# H12R00.net
KiCad netlist of a schematic drawn in EAGLE
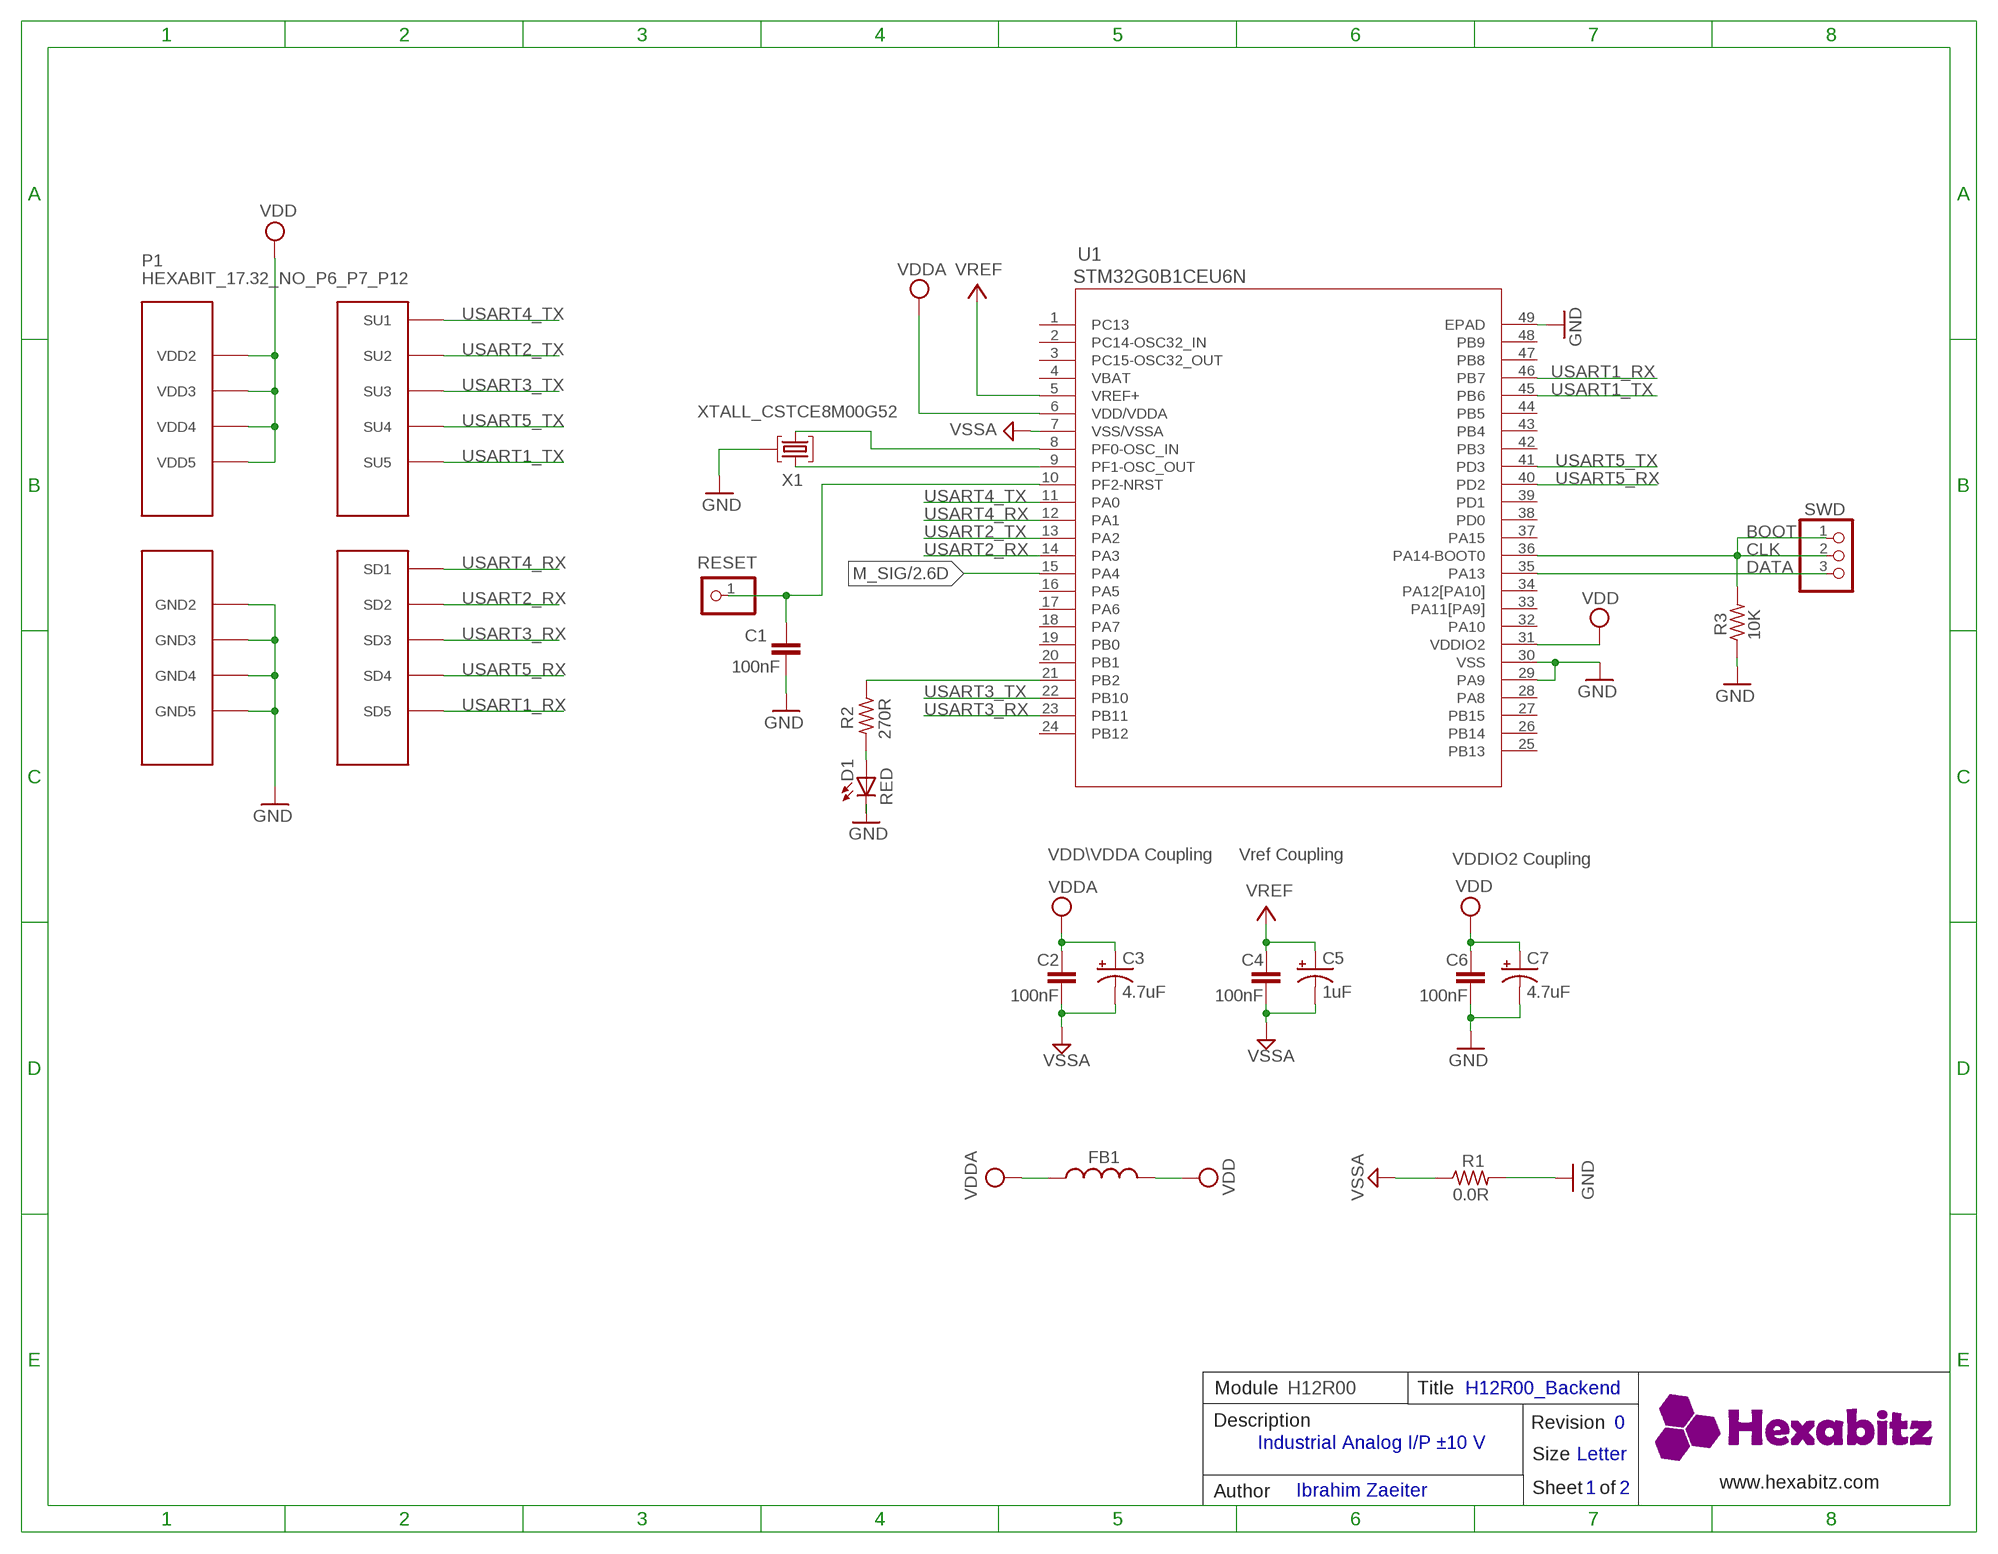
[diagram p0: schematic, sheet 1]
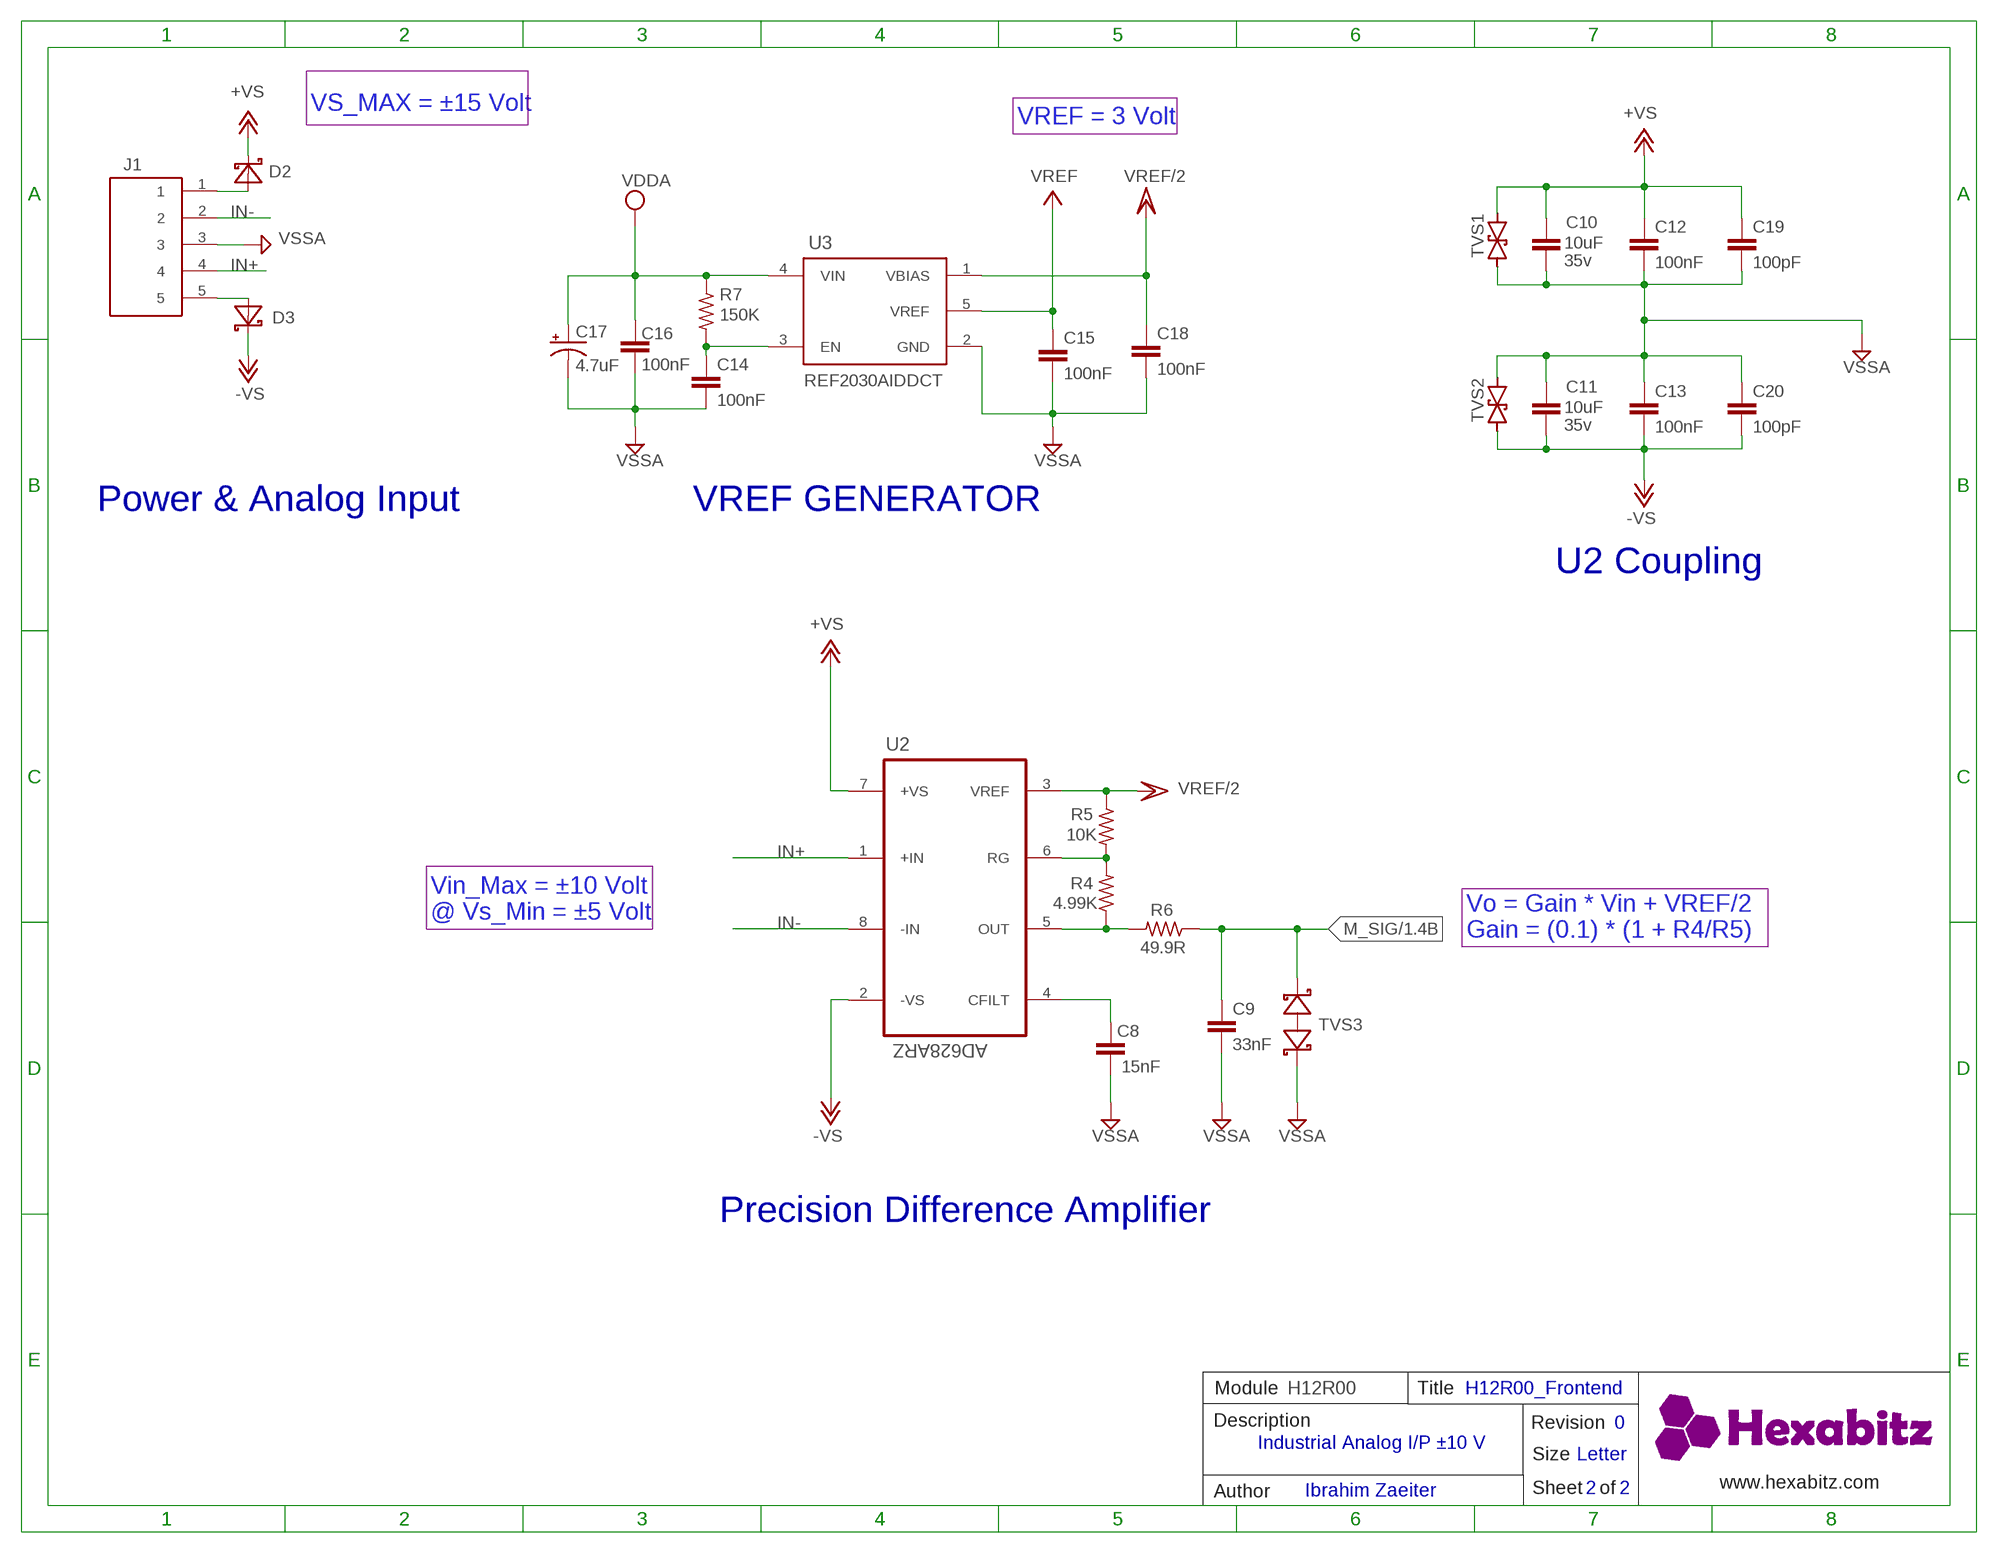
[diagram p1: schematic, sheet 2]

(export (version "E")
  (design (tool "Eeschema 10.0.6"))
  (components
    (comp (ref "C1")
      (value "100nF")
      (footprint "eagle-import:C-0603")
      (libsource (lib "eagle-import") (part "C-0603"))
    )
    (comp (ref "C2")
      (value "100nF")
      (footprint "eagle-import:C-0603")
      (libsource (lib "eagle-import") (part "C-0603"))
    )
    (comp (ref "C3")
      (value "4.7uF")
      (footprint "eagle-import:C-0805-POL")
      (libsource (lib "eagle-import") (part "C-0805-POL"))
    )
    (comp (ref "C4")
      (value "100nF")
      (footprint "eagle-import:C-0603")
      (libsource (lib "eagle-import") (part "C-0603"))
    )
    (comp (ref "C5")
      (value "1uF")
      (footprint "eagle-import:C-0805-POL")
      (libsource (lib "eagle-import") (part "C-0805-POL"))
    )
    (comp (ref "C6")
      (value "100nF")
      (footprint "eagle-import:C-0603")
      (libsource (lib "eagle-import") (part "C-0603"))
    )
    (comp (ref "C7")
      (value "4.7uF")
      (footprint "eagle-import:C-0805-POL")
      (libsource (lib "eagle-import") (part "C-0805-POL"))
    )
    (comp (ref "D1")
      (value "RED")
      (footprint "eagle-import:VLMS1300-GS08")
      (fields
        (field (name "MPN") "VLMS1300-GS08")
        (field (name "MFN") "Vishay")
        (field (name "MPN_1") "VLMS1300-GS08")
        (field (name "OCTOPART_URL") "https://octopart.com/vlms1300-gs08-vishay-21709201?r=sp&s=_gcP4_q8T1SC6PJQPTQ9yA")
      )
      (libsource (lib "eagle-import") (part "VLMS1300-GS08"))
    )
    (comp (ref "FB1")
      (value "FB-0603")
      (footprint "eagle-import:FB-0603")
      (libsource (lib "eagle-import") (part "FB-0603"))
    )
    (comp (ref "P1")
      (value "HEXABIT_17.32_NO_P6_P7_P12")
      (footprint "eagle-import:HEXABIT_17.32_NO_P6_P7_P12")
      (libsource (lib "eagle-import") (part "HEXABIT_?_NO_P6_P7_P1217.32"))
    )
    (comp (ref "R1")
      (value "0.0R")
      (footprint "eagle-import:R-0603")
      (libsource (lib "eagle-import") (part "R-0603"))
    )
    (comp (ref "R2")
      (value "270R")
      (footprint "eagle-import:R-0603")
      (libsource (lib "eagle-import") (part "R-0603"))
    )
    (comp (ref "R3")
      (value "10K")
      (footprint "eagle-import:R-0603")
      (libsource (lib "eagle-import") (part "R-0603"))
    )
    (comp (ref "RESET")
      (value "R")
      (footprint "eagle-import:1X01")
      (fields (field (name "MPN") "87227-1"))
      (libsource (lib "eagle-import") (part "PINHD-1X1"))
    )
    (comp (ref "SWD")
      (value "PINHD-1X3SWD")
      (footprint "eagle-import:SWD")
      (libsource (lib "eagle-import") (part "PINHD-1X3SWD"))
    )
    (comp (ref "U1")
      (value "STM32G0B1CEU6N")
      (footprint "eagle-import:HEXABITZ_ICS_QFN_B1CEU6_STM-L")
      (libsource (lib "eagle-import") (part "STM32G0B1CEU6N"))
    )
    (comp (ref "X1")
      (value "XTALL_CSTCE8M00G52")
      (footprint "eagle-import:XTALL_CSTCE8M00G52")
      (fields (field (name "MPN") "CSTCE8M00G52Z-R0"))
      (libsource (lib "eagle-import") (part "XTALL_CSTCE8M00G52"))
    )
    (comp (ref "C8")
      (value "15nF")
      (footprint "eagle-import:C-0603")
      (libsource (lib "eagle-import") (part "C-0603"))
    )
    (comp (ref "C9")
      (value "33nF")
      (footprint "eagle-import:C-0603")
      (libsource (lib "eagle-import") (part "C-0603"))
    )
    (comp (ref "C10")
      (value "C-0805")
      (footprint "eagle-import:C-0805")
      (fields
        (field (name "CAPACITANCE") "10uF")
        (field (name "MPN") "GRM21BR6YA106ME43K")
        (field (name "VOLTAGE_RATING") "35v")
      )
      (libsource (lib "eagle-import") (part "C-0805"))
    )
    (comp (ref "C11")
      (value "C-0805")
      (footprint "eagle-import:C-0805")
      (fields
        (field (name "CAPACITANCE") "10uF")
        (field (name "MPN") "GRM21BR6YA106ME43K")
        (field (name "VOLTAGE_RATING") "35v")
      )
      (libsource (lib "eagle-import") (part "C-0805"))
    )
    (comp (ref "C12")
      (value "100nF")
      (footprint "eagle-import:C-0603")
      (fields (field (name "MPN") "C1608X7R1H104K080AA"))
      (libsource (lib "eagle-import") (part "C-0603"))
    )
    (comp (ref "C13")
      (value "100nF")
      (footprint "eagle-import:C-0603")
      (fields (field (name "MPN") "C1608X7R1H104K080AA"))
      (libsource (lib "eagle-import") (part "C-0603"))
    )
    (comp (ref "C14")
      (value "100nF")
      (footprint "eagle-import:C-0603")
      (libsource (lib "eagle-import") (part "C-0603"))
    )
    (comp (ref "C15")
      (value "100nF")
      (footprint "eagle-import:C-0603")
      (libsource (lib "eagle-import") (part "C-0603"))
    )
    (comp (ref "C16")
      (value "100nF")
      (footprint "eagle-import:C-0603")
      (libsource (lib "eagle-import") (part "C-0603"))
    )
    (comp (ref "C17")
      (value "4.7uF")
      (footprint "eagle-import:C-0805-POL")
      (libsource (lib "eagle-import") (part "C-0805-POL"))
    )
    (comp (ref "C18")
      (value "100nF")
      (footprint "eagle-import:C-0603")
      (libsource (lib "eagle-import") (part "C-0603"))
    )
    (comp (ref "C19")
      (value "100pF")
      (footprint "eagle-import:C-0603")
      (fields (field (name "MPN") "C1608X7R1H104K080AA"))
      (libsource (lib "eagle-import") (part "C-0603"))
    )
    (comp (ref "C20")
      (value "100pF")
      (footprint "eagle-import:C-0603")
      (fields (field (name "MPN") "C1608X7R1H104K080AA"))
      (libsource (lib "eagle-import") (part "C-0603"))
    )
    (comp (ref "D2")
      (value "DIOD-SOD-123")
      (footprint "eagle-import:SOD123")
      (libsource (lib "eagle-import") (part "DIOD-SOD-123"))
    )
    (comp (ref "D3")
      (value "DIOD-SOD-123")
      (footprint "eagle-import:SOD123")
      (libsource (lib "eagle-import") (part "DIOD-SOD-123"))
    )
    (comp (ref "J1")
      (value "1984646")
      (footprint "eagle-import:1984646")
      (fields (field (name "MOUSER_PART_NUMBER") "651-1984646"))
      (libsource (lib "eagle-import") (part "1984646"))
    )
    (comp (ref "R4")
      (value "4.99K")
      (footprint "eagle-import:R-0603")
      (libsource (lib "eagle-import") (part "R-0603"))
    )
    (comp (ref "R5")
      (value "10K")
      (footprint "eagle-import:R-0603")
      (libsource (lib "eagle-import") (part "R-0603"))
    )
    (comp (ref "R6")
      (value "49.9R")
      (footprint "eagle-import:R-0603")
      (libsource (lib "eagle-import") (part "R-0603"))
    )
    (comp (ref "R7")
      (value "150K")
      (footprint "eagle-import:R-0603")
      (libsource (lib "eagle-import") (part "R-0603"))
    )
    (comp (ref "TVS1")
      (value "SMBJ30CA")
      (footprint "eagle-import:DO214AA")
      (libsource (lib "eagle-import") (part "SMBJ30CA"))
    )
    (comp (ref "TVS2")
      (value "SMBJ30CA")
      (footprint "eagle-import:DO214AA")
      (libsource (lib "eagle-import") (part "SMBJ30CA"))
    )
    (comp (ref "TVS3")
      (value "BOURNS_CDSOD323-T03SCBOURNS_CDSOD323-T03SC_0_0")
      (footprint "eagle-import:BOURNS_CDSOD323-T03SC_0")
      (fields (field (name "MPN") "CDSOD323-T03SC"))
      (libsource (lib "eagle-import") (part "BOURNS_CDSOD323-T03SCBOURNS_CDSOD323-T03SC_0_0"))
    )
    (comp (ref "U2")
      (value "AD628ARZ")
      (footprint "eagle-import:SOIC127P600X175-8N")
      (libsource (lib "eagle-import") (part "AD628ARZ"))
    )
    (comp (ref "U3")
      (value "TEXAS_INSTRUMENTS_REF2033AIDDCRTEXAS_INSTRUMENTS_REF2033AIDDCR_0_2")
      (footprint "eagle-import:TEXAS_INSTRUMENTS_REF2033AIDDCR_2")
      (fields
        (field (name "MPN") "REF2033AIDDCR")
        (field (name "MPN_1") "REF2030AIDDCT")
        (field (name "OUTPUT_VOLTAGE") "1.5/3.0V")
      )
      (libsource (lib "eagle-import") (part "TEXAS_INSTRUMENTS_REF2033AIDDCRTEXAS_INSTRUMENTS_REF2033AIDDCR_0_2"))
    )
  )
  (nets
    (net (code "1") (name "+VS") (class "Default")
      (node (ref "C10") (pin "1") (pinfunction "1_1") (pintype "passive"))
      (node (ref "C12") (pin "1") (pinfunction "1_1") (pintype "passive"))
      (node (ref "C19") (pin "1") (pinfunction "1_1") (pintype "passive"))
      (node (ref "D2") (pin "2") (pinfunction "C_2") (pintype "passive"))
      (node (ref "TVS1") (pin "C") (pinfunction "2_C") (pintype "passive"))
      (node (ref "U2") (pin "7") (pinfunction "+VS_7") (pintype "power_in"))
    )
    (net (code "2") (name "-VS") (class "Default")
      (node (ref "C11") (pin "2") (pinfunction "2_2") (pintype "passive"))
      (node (ref "C13") (pin "2") (pinfunction "2_2") (pintype "passive"))
      (node (ref "C20") (pin "2") (pinfunction "2_2") (pintype "passive"))
      (node (ref "D3") (pin "2") (pinfunction "C_2") (pintype "passive"))
      (node (ref "TVS2") (pin "A") (pinfunction "1_A") (pintype "passive"))
      (node (ref "U2") (pin "2") (pinfunction "-VS_2") (pintype "power_in"))
    )
    (net (code "3") (name "CLK") (class "Default")
      (node (ref "R3") (pin "2") (pinfunction "2_2") (pintype "passive"))
      (node (ref "SWD") (pin "1") (pinfunction "1_1") (pintype "passive"))
      (node (ref "SWD") (pin "2") (pinfunction "2_2") (pintype "passive"))
      (node (ref "U1") (pin "36") (pinfunction "PA14-BOOT0_36") (pintype "bidirectional"))
    )
    (net (code "4") (name "DATA") (class "Default")
      (node (ref "SWD") (pin "3") (pinfunction "3_3") (pintype "passive"))
      (node (ref "U1") (pin "35") (pinfunction "PA13_35") (pintype "bidirectional"))
    )
    (net (code "5") (name "GND") (class "Default")
      (node (ref "C1") (pin "2") (pinfunction "2_2") (pintype "passive"))
      (node (ref "C6") (pin "2") (pinfunction "2_2") (pintype "passive"))
      (node (ref "C7") (pin "2") (pinfunction "-_2") (pintype "passive"))
      (node (ref "D1") (pin "C") (pinfunction "C_C") (pintype "passive"))
      (node (ref "P1") (pin "PAD_PD10") (pinfunction "GND4_PAD_PD10") (pintype "power_in"))
      (node (ref "P1") (pin "PAD_PD11") (pinfunction "GND5_PAD_PD11") (pintype "power_in"))
      (node (ref "P1") (pin "PAD_PD8") (pinfunction "GND2_PAD_PD8") (pintype "power_in"))
      (node (ref "P1") (pin "PAD_PD9") (pinfunction "GND3_PAD_PD9") (pintype "power_in"))
      (node (ref "R1") (pin "2") (pinfunction "2_2") (pintype "passive"))
      (node (ref "R3") (pin "1") (pinfunction "1_1") (pintype "passive"))
      (node (ref "U1") (pin "29") (pinfunction "PA9_29") (pintype "bidirectional"))
      (node (ref "U1") (pin "30") (pinfunction "VSS_30") (pintype "passive"))
      (node (ref "U1") (pin "49") (pinfunction "EPAD_49") (pintype "passive"))
      (node (ref "X1") (pin "P$2") (pinfunction "2_P$2") (pintype "passive"))
    )
    (net (code "6") (name "IN+") (class "Default")
      (node (ref "J1") (pin "4") (pinfunction "4_4") (pintype "bidirectional"))
      (node (ref "U2") (pin "1") (pinfunction "+IN_1") (pintype "input"))
    )
    (net (code "7") (name "IN-") (class "Default")
      (node (ref "J1") (pin "2") (pinfunction "2_2") (pintype "bidirectional"))
      (node (ref "U2") (pin "8") (pinfunction "-IN_8") (pintype "input"))
    )
    (net (code "8") (name "M_SIG") (class "Default")
      (node (ref "C9") (pin "1") (pinfunction "1_1") (pintype "passive"))
      (node (ref "R6") (pin "1") (pinfunction "1_1") (pintype "passive"))
      (node (ref "TVS3") (pin "2") (pinfunction "C_2") (pintype "passive"))
      (node (ref "U1") (pin "15") (pinfunction "PA4_15") (pintype "bidirectional"))
    )
    (net (code "9") (name "Net-(D1-PadA)") (class "Default")
      (node (ref "D1") (pin "A") (pinfunction "A_A") (pintype "passive"))
      (node (ref "R2") (pin "2") (pinfunction "2_2") (pintype "passive"))
    )
    (net (code "10") (name "Net-(D2-A)") (class "Default")
      (node (ref "D2") (pin "1") (pinfunction "A_1") (pintype "passive"))
      (node (ref "J1") (pin "1") (pinfunction "1_1") (pintype "bidirectional"))
    )
    (net (code "11") (name "Net-(D3-A)") (class "Default")
      (node (ref "D3") (pin "1") (pinfunction "A_1") (pintype "passive"))
      (node (ref "J1") (pin "5") (pinfunction "5_5") (pintype "bidirectional"))
    )
    (net (code "12") (name "Net-(U1-PB2)") (class "Default")
      (node (ref "R2") (pin "1") (pinfunction "1_1") (pintype "passive"))
      (node (ref "U1") (pin "21") (pinfunction "PB2_21") (pintype "bidirectional"))
    )
    (net (code "13") (name "Net-(U1-PF0-OSC_IN)") (class "Default")
      (node (ref "U1") (pin "8") (pinfunction "PF0-OSC_IN_8") (pintype "bidirectional"))
      (node (ref "X1") (pin "P$3") (pinfunction "3_P$3") (pintype "passive"))
    )
    (net (code "14") (name "Net-(U1-PF1-OSC_OUT)") (class "Default")
      (node (ref "U1") (pin "9") (pinfunction "PF1-OSC_OUT_9") (pintype "bidirectional"))
      (node (ref "X1") (pin "P$1") (pinfunction "1_P$1") (pintype "passive"))
    )
    (net (code "15") (name "Net-(U1-PF2-NRST)") (class "Default")
      (node (ref "C1") (pin "1") (pinfunction "1_1") (pintype "passive"))
      (node (ref "RESET") (pin "1") (pinfunction "1_1") (pintype "passive"))
      (node (ref "U1") (pin "10") (pinfunction "PF2-NRST_10") (pintype "bidirectional"))
    )
    (net (code "16") (name "Net-(U2-CFILT)") (class "Default")
      (node (ref "C8") (pin "1") (pinfunction "1_1") (pintype "passive"))
      (node (ref "U2") (pin "4") (pinfunction "CFILT_4") (pintype "passive"))
    )
    (net (code "17") (name "Net-(U2-OUT)") (class "Default")
      (node (ref "R4") (pin "1") (pinfunction "1_1") (pintype "passive"))
      (node (ref "R6") (pin "2") (pinfunction "2_2") (pintype "passive"))
      (node (ref "U2") (pin "5") (pinfunction "OUT_5") (pintype "output"))
    )
    (net (code "18") (name "Net-(U2-RG)") (class "Default")
      (node (ref "R4") (pin "2") (pinfunction "2_2") (pintype "passive"))
      (node (ref "R5") (pin "2") (pinfunction "2_2") (pintype "passive"))
      (node (ref "U2") (pin "6") (pinfunction "RG_6") (pintype "passive"))
    )
    (net (code "19") (name "Net-(U3-EN)") (class "Default")
      (node (ref "C14") (pin "1") (pinfunction "1_1") (pintype "passive"))
      (node (ref "R7") (pin "2") (pinfunction "2_2") (pintype "passive"))
      (node (ref "U3") (pin "3") (pinfunction "EN_3") (pintype "input"))
    )
    (net (code "20") (name "USART1_RX") (class "Default")
      (node (ref "P1") (pin "PAD_PD5") (pinfunction "SD5_PAD_PD5") (pintype "bidirectional"))
      (node (ref "U1") (pin "46") (pinfunction "PB7_46") (pintype "bidirectional"))
    )
    (net (code "21") (name "USART1_TX") (class "Default")
      (node (ref "P1") (pin "PAD_PU5") (pinfunction "SU5_PAD_PU5") (pintype "bidirectional"))
      (node (ref "U1") (pin "45") (pinfunction "PB6_45") (pintype "bidirectional"))
    )
    (net (code "22") (name "USART2_RX") (class "Default")
      (node (ref "P1") (pin "PAD_PD2") (pinfunction "SD2_PAD_PD2") (pintype "bidirectional"))
      (node (ref "U1") (pin "14") (pinfunction "PA3_14") (pintype "bidirectional"))
    )
    (net (code "23") (name "USART2_TX") (class "Default")
      (node (ref "P1") (pin "PAD_PU2") (pinfunction "SU2_PAD_PU2") (pintype "bidirectional"))
      (node (ref "U1") (pin "13") (pinfunction "PA2_13") (pintype "bidirectional"))
    )
    (net (code "24") (name "USART3_RX") (class "Default")
      (node (ref "P1") (pin "PAD_PD3") (pinfunction "SD3_PAD_PD3") (pintype "bidirectional"))
      (node (ref "U1") (pin "23") (pinfunction "PB11_23") (pintype "bidirectional"))
    )
    (net (code "25") (name "USART3_TX") (class "Default")
      (node (ref "P1") (pin "PAD_PU3") (pinfunction "SU3_PAD_PU3") (pintype "bidirectional"))
      (node (ref "U1") (pin "22") (pinfunction "PB10_22") (pintype "bidirectional"))
    )
    (net (code "26") (name "USART4_RX") (class "Default")
      (node (ref "P1") (pin "PAD_PD1") (pinfunction "SD1_PAD_PD1") (pintype "bidirectional"))
      (node (ref "U1") (pin "12") (pinfunction "PA1_12") (pintype "bidirectional"))
    )
    (net (code "27") (name "USART4_TX") (class "Default")
      (node (ref "P1") (pin "PAD_PU1") (pinfunction "SU1_PAD_PU1") (pintype "bidirectional"))
      (node (ref "U1") (pin "11") (pinfunction "PA0_11") (pintype "bidirectional"))
    )
    (net (code "28") (name "USART5_RX") (class "Default")
      (node (ref "P1") (pin "PAD_PD4") (pinfunction "SD4_PAD_PD4") (pintype "bidirectional"))
      (node (ref "U1") (pin "40") (pinfunction "PD2_40") (pintype "bidirectional"))
    )
    (net (code "29") (name "USART5_TX") (class "Default")
      (node (ref "P1") (pin "PAD_PU4") (pinfunction "SU4_PAD_PU4") (pintype "bidirectional"))
      (node (ref "U1") (pin "41") (pinfunction "PD3_41") (pintype "bidirectional"))
    )
    (net (code "30") (name "VBAT") (class "Default")
      (node (ref "U1") (pin "4") (pinfunction "VBAT_4") (pintype "power_in"))
    )
    (net (code "31") (name "VDD") (class "Default")
      (node (ref "C6") (pin "1") (pinfunction "1_1") (pintype "passive"))
      (node (ref "C7") (pin "1") (pinfunction "+_1") (pintype "passive"))
      (node (ref "FB1") (pin "2") (pinfunction "2_2") (pintype "passive"))
      (node (ref "P1") (pin "PAD_PU10") (pinfunction "VDD4_PAD_PU10") (pintype "power_in"))
      (node (ref "P1") (pin "PAD_PU11") (pinfunction "VDD5_PAD_PU11") (pintype "power_in"))
      (node (ref "P1") (pin "PAD_PU8") (pinfunction "VDD2_PAD_PU8") (pintype "power_in"))
      (node (ref "P1") (pin "PAD_PU9") (pinfunction "VDD3_PAD_PU9") (pintype "power_in"))
      (node (ref "U1") (pin "31") (pinfunction "VDDIO2_31") (pintype "power_in"))
    )
    (net (code "32") (name "VDDA") (class "Default")
      (node (ref "C16") (pin "1") (pinfunction "1_1") (pintype "passive"))
      (node (ref "C17") (pin "1") (pinfunction "+_1") (pintype "passive"))
      (node (ref "C2") (pin "1") (pinfunction "1_1") (pintype "passive"))
      (node (ref "C3") (pin "1") (pinfunction "+_1") (pintype "passive"))
      (node (ref "FB1") (pin "1") (pinfunction "1_1") (pintype "passive"))
      (node (ref "R7") (pin "1") (pinfunction "1_1") (pintype "passive"))
      (node (ref "U1") (pin "6") (pinfunction "VDD/VDDA_6") (pintype "power_in"))
      (node (ref "U3") (pin "4") (pinfunction "VIN_4") (pintype "power_in"))
    )
    (net (code "33") (name "VREF") (class "Default")
      (node (ref "C15") (pin "1") (pinfunction "1_1") (pintype "passive"))
      (node (ref "C4") (pin "1") (pinfunction "1_1") (pintype "passive"))
      (node (ref "C5") (pin "1") (pinfunction "+_1") (pintype "passive"))
      (node (ref "U1") (pin "5") (pinfunction "VREF+_5") (pintype "power_in"))
      (node (ref "U3") (pin "5") (pinfunction "VREF_5") (pintype "power_in"))
    )
    (net (code "34") (name "VREF{slash}2") (class "Default")
      (node (ref "C18") (pin "1") (pinfunction "1_1") (pintype "passive"))
      (node (ref "R5") (pin "1") (pinfunction "1_1") (pintype "passive"))
      (node (ref "U2") (pin "3") (pinfunction "VREF_3") (pintype "passive"))
      (node (ref "U3") (pin "1") (pinfunction "VBIAS_1") (pintype "power_in"))
    )
    (net (code "35") (name "VSSA") (class "Default")
      (node (ref "C10") (pin "2") (pinfunction "2_2") (pintype "passive"))
      (node (ref "C11") (pin "1") (pinfunction "1_1") (pintype "passive"))
      (node (ref "C12") (pin "2") (pinfunction "2_2") (pintype "passive"))
      (node (ref "C13") (pin "1") (pinfunction "1_1") (pintype "passive"))
      (node (ref "C14") (pin "2") (pinfunction "2_2") (pintype "passive"))
      (node (ref "C15") (pin "2") (pinfunction "2_2") (pintype "passive"))
      (node (ref "C16") (pin "2") (pinfunction "2_2") (pintype "passive"))
      (node (ref "C17") (pin "2") (pinfunction "-_2") (pintype "passive"))
      (node (ref "C18") (pin "2") (pinfunction "2_2") (pintype "passive"))
      (node (ref "C19") (pin "2") (pinfunction "2_2") (pintype "passive"))
      (node (ref "C2") (pin "2") (pinfunction "2_2") (pintype "passive"))
      (node (ref "C20") (pin "1") (pinfunction "1_1") (pintype "passive"))
      (node (ref "C3") (pin "2") (pinfunction "-_2") (pintype "passive"))
      (node (ref "C4") (pin "2") (pinfunction "2_2") (pintype "passive"))
      (node (ref "C5") (pin "2") (pinfunction "-_2") (pintype "passive"))
      (node (ref "C8") (pin "2") (pinfunction "2_2") (pintype "passive"))
      (node (ref "C9") (pin "2") (pinfunction "2_2") (pintype "passive"))
      (node (ref "J1") (pin "3") (pinfunction "3_3") (pintype "bidirectional"))
      (node (ref "R1") (pin "1") (pinfunction "1_1") (pintype "passive"))
      (node (ref "TVS1") (pin "A") (pinfunction "1_A") (pintype "passive"))
      (node (ref "TVS2") (pin "C") (pinfunction "2_C") (pintype "passive"))
      (node (ref "TVS3") (pin "1") (pinfunction "A_1") (pintype "passive"))
      (node (ref "U1") (pin "7") (pinfunction "VSS/VSSA_7") (pintype "passive"))
      (node (ref "U3") (pin "2") (pinfunction "GND_2") (pintype "power_in"))
    )
    (net (code "36") (name "unconnected-(U1-PA5-Pad16)") (class "Default")
      (node (ref "U1") (pin "16") (pinfunction "PA5_16") (pintype "bidirectional"))
    )
    (net (code "37") (name "unconnected-(U1-PA6-Pad17)") (class "Default")
      (node (ref "U1") (pin "17") (pinfunction "PA6_17") (pintype "bidirectional"))
    )
    (net (code "38") (name "unconnected-(U1-PA7-Pad18)") (class "Default")
      (node (ref "U1") (pin "18") (pinfunction "PA7_18") (pintype "bidirectional"))
    )
    (net (code "39") (name "unconnected-(U1-PA8-Pad28)") (class "Default")
      (node (ref "U1") (pin "28") (pinfunction "PA8_28") (pintype "bidirectional"))
    )
    (net (code "40") (name "unconnected-(U1-PA10-Pad32)") (class "Default")
      (node (ref "U1") (pin "32") (pinfunction "PA10_32") (pintype "bidirectional"))
    )
    (net (code "41") (name "unconnected-(U1-PA11[PA9]-Pad33)") (class "Default")
      (node (ref "U1") (pin "33") (pinfunction "PA11[PA9]_33") (pintype "bidirectional"))
    )
    (net (code "42") (name "unconnected-(U1-PA12[PA10]-Pad34)") (class "Default")
      (node (ref "U1") (pin "34") (pinfunction "PA12[PA10]_34") (pintype "bidirectional"))
    )
    (net (code "43") (name "unconnected-(U1-PA15-Pad37)") (class "Default")
      (node (ref "U1") (pin "37") (pinfunction "PA15_37") (pintype "bidirectional"))
    )
    (net (code "44") (name "unconnected-(U1-PB0-Pad19)") (class "Default")
      (node (ref "U1") (pin "19") (pinfunction "PB0_19") (pintype "bidirectional"))
    )
    (net (code "45") (name "unconnected-(U1-PB1-Pad20)") (class "Default")
      (node (ref "U1") (pin "20") (pinfunction "PB1_20") (pintype "bidirectional"))
    )
    (net (code "46") (name "unconnected-(U1-PB3-Pad42)") (class "Default")
      (node (ref "U1") (pin "42") (pinfunction "PB3_42") (pintype "bidirectional"))
    )
    (net (code "47") (name "unconnected-(U1-PB4-Pad43)") (class "Default")
      (node (ref "U1") (pin "43") (pinfunction "PB4_43") (pintype "bidirectional"))
    )
    (net (code "48") (name "unconnected-(U1-PB5-Pad44)") (class "Default")
      (node (ref "U1") (pin "44") (pinfunction "PB5_44") (pintype "bidirectional"))
    )
    (net (code "49") (name "unconnected-(U1-PB8-Pad47)") (class "Default")
      (node (ref "U1") (pin "47") (pinfunction "PB8_47") (pintype "bidirectional"))
    )
    (net (code "50") (name "unconnected-(U1-PB9-Pad48)") (class "Default")
      (node (ref "U1") (pin "48") (pinfunction "PB9_48") (pintype "bidirectional"))
    )
    (net (code "51") (name "unconnected-(U1-PB12-Pad24)") (class "Default")
      (node (ref "U1") (pin "24") (pinfunction "PB12_24") (pintype "bidirectional"))
    )
    (net (code "52") (name "unconnected-(U1-PB13-Pad25)") (class "Default")
      (node (ref "U1") (pin "25") (pinfunction "PB13_25") (pintype "bidirectional"))
    )
    (net (code "53") (name "unconnected-(U1-PB14-Pad26)") (class "Default")
      (node (ref "U1") (pin "26") (pinfunction "PB14_26") (pintype "bidirectional"))
    )
    (net (code "54") (name "unconnected-(U1-PB15-Pad27)") (class "Default")
      (node (ref "U1") (pin "27") (pinfunction "PB15_27") (pintype "bidirectional"))
    )
    (net (code "55") (name "unconnected-(U1-PC13-Pad1)") (class "Default")
      (node (ref "U1") (pin "1") (pinfunction "PC13_1") (pintype "bidirectional"))
    )
    (net (code "56") (name "unconnected-(U1-PC14-OSC32_IN-Pad2)") (class "Default")
      (node (ref "U1") (pin "2") (pinfunction "PC14-OSC32_IN_2") (pintype "bidirectional"))
    )
    (net (code "57") (name "unconnected-(U1-PC15-OSC32_OUT-Pad3)") (class "Default")
      (node (ref "U1") (pin "3") (pinfunction "PC15-OSC32_OUT_3") (pintype "bidirectional"))
    )
    (net (code "58") (name "unconnected-(U1-PD0-Pad38)") (class "Default")
      (node (ref "U1") (pin "38") (pinfunction "PD0_38") (pintype "bidirectional"))
    )
    (net (code "59") (name "unconnected-(U1-PD1-Pad39)") (class "Default")
      (node (ref "U1") (pin "39") (pinfunction "PD1_39") (pintype "bidirectional"))
    )
  )
)
